# 02-MCU.net
KiCad netlist of a schematic drawn in Altium Designer
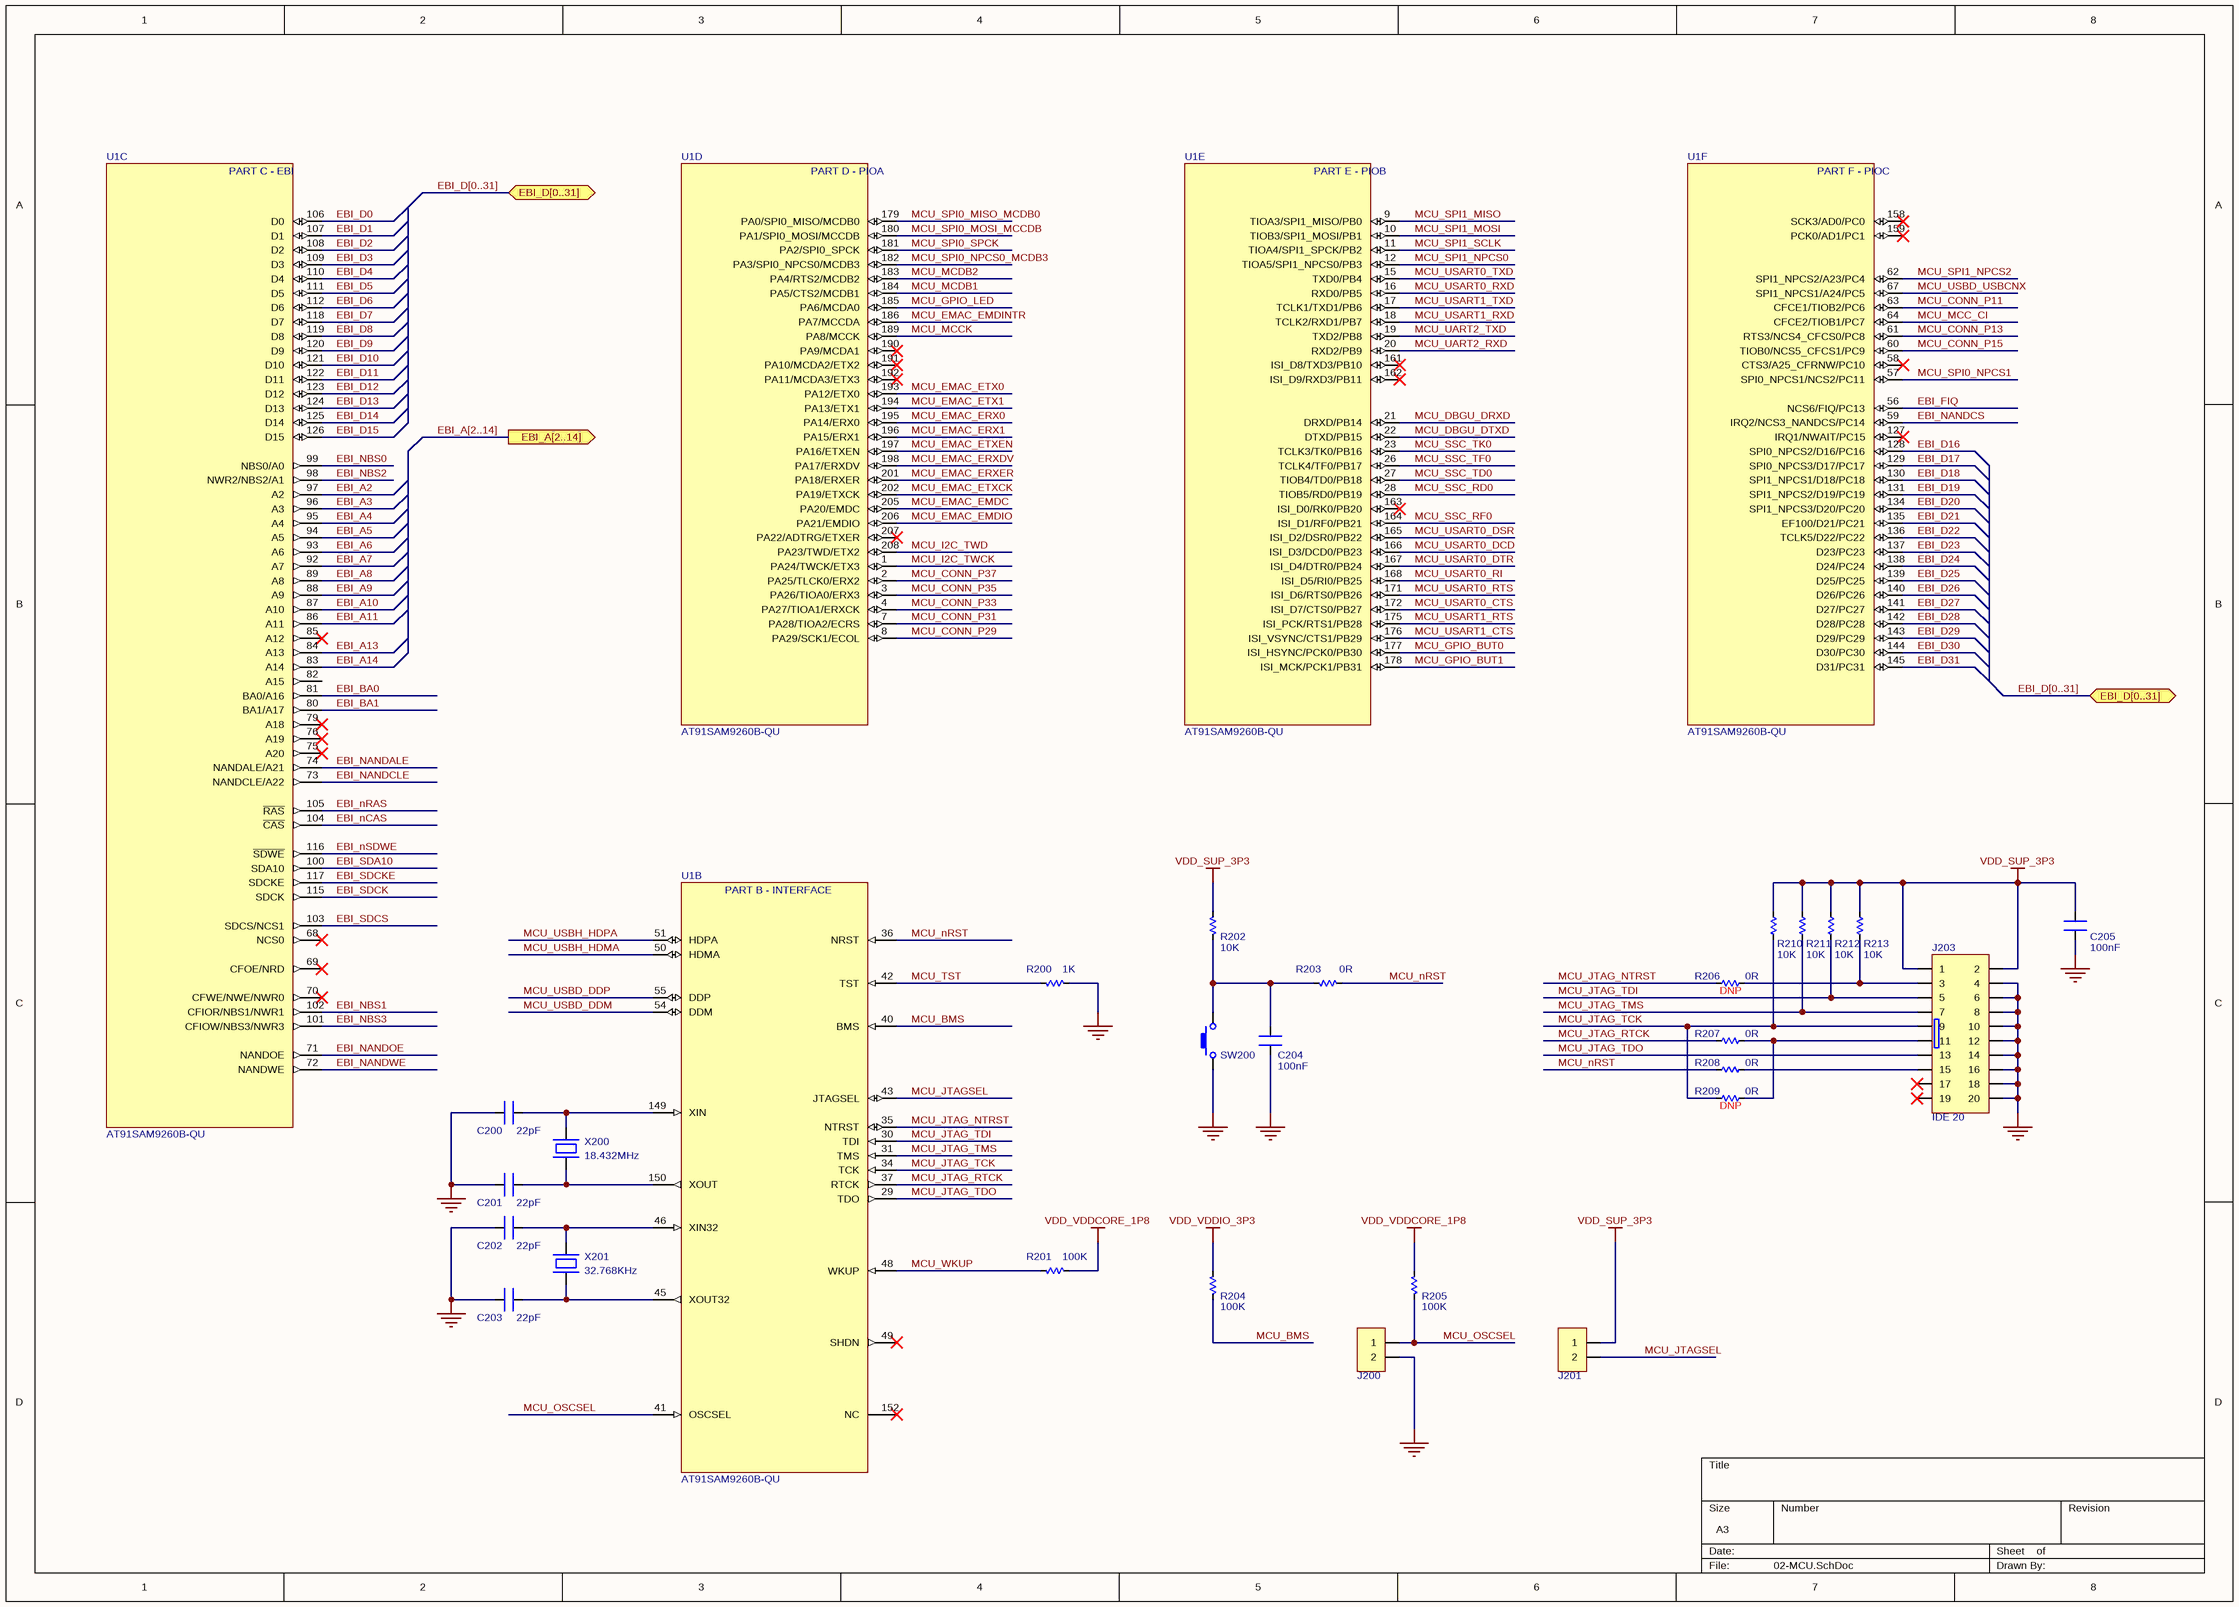
[diagram p0: 02-MCU.SchDoc]

(export (version "E")
  (design (tool "Eeschema 10.0.6"))
  (components
    (comp (ref "C200")
      (value "22pF")
      (footprint "CN-SMD-0603")
      (description "Ceramic Capacitor SMD 0603 22pF ±20% 10V")
      (fields (field (name "Comment") "Capacitor"))
      (libsource (lib "AS50") (part "Cap"))
    )
    (comp (ref "C201")
      (value "22pF")
      (footprint "CN-SMD-0603")
      (description "Ceramic Capacitor SMD 0603 22pF ±20% 10V")
      (fields (field (name "Comment") "Capacitor"))
      (libsource (lib "AS50") (part "Cap"))
    )
    (comp (ref "C202")
      (value "22pF")
      (footprint "CN-SMD-0603")
      (description "Ceramic Capacitor SMD 0603 22pF ±20% 10V")
      (fields (field (name "Comment") "Capacitor"))
      (libsource (lib "AS50") (part "Cap"))
    )
    (comp (ref "C203")
      (value "22pF")
      (footprint "CN-SMD-0603")
      (description "Ceramic Capacitor SMD 0603 22pF ±20% 10V")
      (fields (field (name "Comment") "Capacitor"))
      (libsource (lib "AS50") (part "Cap"))
    )
    (comp (ref "C204")
      (value "100nF")
      (footprint "CN-SMD-0603")
      (description "Ceramic Capacitor SMD 0603 100nF ±20% 10V")
      (fields (field (name "Comment") "Capacitor"))
      (libsource (lib "AS50") (part "Cap"))
    )
    (comp (ref "C205")
      (value "100nF")
      (footprint "CN-SMD-0603")
      (description "Ceramic Capacitor SMD 0603 100nF ±20% 10V")
      (fields (field (name "Comment") "Capacitor"))
      (libsource (lib "AS50") (part "Cap"))
    )
    (comp (ref "J200")
      (value "JP2")
      (footprint "JP2-C1T")
      (description "Single 2-pin jumper")
      (libsource (lib "AS50") (part "JP2"))
    )
    (comp (ref "J201")
      (value "JP2")
      (footprint "JP2-C1T")
      (description "Single 2-pin jumper")
      (libsource (lib "AS50") (part "JP2"))
    )
    (comp (ref "J203")
      (value "IDE 20")
      (footprint "IDE-20V")
      (description "IDE-20 male 2.54mm right-angle header")
      (libsource (lib "AS50") (part "IDE 20"))
    )
    (comp (ref "R200")
      (value "1K")
      (footprint "RES-SMD-0603")
      (description "Resistor SMD 0603 1K 1% 0.1W")
      (fields (field (name "Comment") "Resistor"))
      (libsource (lib "AS50") (part "Res"))
    )
    (comp (ref "R201")
      (value "100K")
      (footprint "RES-SMD-0603")
      (description "Resistor SMD 0603 100K 1% 0.1W")
      (fields (field (name "Comment") "Resistor"))
      (libsource (lib "AS50") (part "Res"))
    )
    (comp (ref "R202")
      (value "10K")
      (footprint "RES-SMD-0603")
      (description "Resistor SMD 0603 10K 1% 0.1W")
      (fields (field (name "Comment") "Resistor"))
      (libsource (lib "AS50") (part "Res"))
    )
    (comp (ref "R203")
      (value "0R")
      (footprint "RES-SMD-0603")
      (description "Resistor SMD 0603 0R 1% 0.1W")
      (fields (field (name "Comment") "Resistor"))
      (libsource (lib "AS50") (part "Res"))
    )
    (comp (ref "R204")
      (value "100K")
      (footprint "RES-SMD-0603")
      (description "Resistor SMD 0603 100K 1% 0.1W")
      (fields (field (name "Comment") "Resistor"))
      (libsource (lib "AS50") (part "Res"))
    )
    (comp (ref "R205")
      (value "100K")
      (footprint "RES-SMD-0603")
      (description "Resistor SMD 0603 100K 1% 0.1W")
      (fields (field (name "Comment") "Resistor"))
      (libsource (lib "AS50") (part "Res"))
    )
    (comp (ref "R206")
      (value "0R")
      (footprint "RES-SMD-0603")
      (description "Resistor SMD 0603 0R 1% 0.1W")
      (fields (field (name "Comment") "Resistor"))
      (libsource (lib "AS50") (part "Res"))
    )
    (comp (ref "R207")
      (value "0R")
      (footprint "RES-SMD-0603")
      (description "Resistor SMD 0603 0R 1% 0.1W")
      (fields (field (name "Comment") "Resistor"))
      (libsource (lib "AS50") (part "Res"))
    )
    (comp (ref "R208")
      (value "0R")
      (footprint "RES-SMD-0603")
      (description "Resistor SMD 0603 0R 1% 0.1W")
      (fields (field (name "Comment") "Resistor"))
      (libsource (lib "AS50") (part "Res"))
    )
    (comp (ref "R209")
      (value "0R")
      (footprint "RES-SMD-0603")
      (description "Resistor SMD 0603 0R 1% 0.1W")
      (fields (field (name "Comment") "Resistor"))
      (libsource (lib "AS50") (part "Res"))
    )
    (comp (ref "R210")
      (value "10K")
      (footprint "RES-SMD-0603")
      (description "Resistor SMD 0603 10K 1% 0.1W")
      (fields (field (name "Comment") "Resistor"))
      (libsource (lib "AS50") (part "Res"))
    )
    (comp (ref "R211")
      (value "10K")
      (footprint "RES-SMD-0603")
      (description "Resistor SMD 0603 10K 1% 0.1W")
      (fields (field (name "Comment") "Resistor"))
      (libsource (lib "AS50") (part "Res"))
    )
    (comp (ref "R212")
      (value "10K")
      (footprint "RES-SMD-0603")
      (description "Resistor SMD 0603 10K 1% 0.1W")
      (fields (field (name "Comment") "Resistor"))
      (libsource (lib "AS50") (part "Res"))
    )
    (comp (ref "R213")
      (value "10K")
      (footprint "RES-SMD-0603")
      (description "Resistor SMD 0603 10K 1% 0.1W")
      (fields (field (name "Comment") "Resistor"))
      (libsource (lib "AS50") (part "Res"))
    )
    (comp (ref "SW200")
      (value "SW2")
      (footprint "SW2-SMD-3x4x2M")
      (description "Switch 2-pin SMD 3x4x2mm")
      (libsource (lib "AS50") (part "SW2"))
    )
    (comp (ref "U1")
      (value "AT91SAM9260B-QU")
      (footprint "PQFP50P3060X3060X410-208N")
      (description "AT91 Series 180 MHz 32 kB Flash 8 kB SRAM 32-Bit Microcontroller - PQFP-208")
      (fields (field (name "MF") "Microchip"))
      (libsource (lib "AS50") (part "AT91SAM9260B-QU"))
    )
    (comp (ref "X200")
      (value "18.432MHz")
      (footprint "XT-SMD-5032-2P")
      (description "Crystal Oscillator 18.432MHz SMD-5032 2-pin")
      (fields (field (name "Comment") "Crystal"))
      (libsource (lib "AS50") (part "XT2"))
    )
    (comp (ref "X201")
      (value "32.768KHz")
      (footprint "XT-SMD-FC-135")
      (description "Crystal Oscillator 32.768KHz FC-135 2-pin")
      (fields (field (name "Comment") "Crystal"))
      (libsource (lib "AS50") (part "XT2"))
    )
  )
  (nets
    (net (code "2") (name "/EBI_A2") (class "Default")
      (node (ref "U1") (pin "97") (pinfunction "A2_97") (pintype "output"))
    )
    (net (code "3") (name "/EBI_A3") (class "Default")
      (node (ref "U1") (pin "96") (pinfunction "A3_96") (pintype "output"))
    )
    (net (code "4") (name "/EBI_A4") (class "Default")
      (node (ref "U1") (pin "95") (pinfunction "A4_95") (pintype "output"))
    )
    (net (code "5") (name "/EBI_A5") (class "Default")
      (node (ref "U1") (pin "94") (pinfunction "A5_94") (pintype "output"))
    )
    (net (code "6") (name "/EBI_A6") (class "Default")
      (node (ref "U1") (pin "93") (pinfunction "A6_93") (pintype "output"))
    )
    (net (code "7") (name "/EBI_A7") (class "Default")
      (node (ref "U1") (pin "92") (pinfunction "A7_92") (pintype "output"))
    )
    (net (code "8") (name "/EBI_A8") (class "Default")
      (node (ref "U1") (pin "89") (pinfunction "A8_89") (pintype "output"))
    )
    (net (code "9") (name "/EBI_A9") (class "Default")
      (node (ref "U1") (pin "88") (pinfunction "A9_88") (pintype "output"))
    )
    (net (code "10") (name "/EBI_A10") (class "Default")
      (node (ref "U1") (pin "87") (pinfunction "A10_87") (pintype "output"))
    )
    (net (code "11") (name "/EBI_A11") (class "Default")
      (node (ref "U1") (pin "86") (pinfunction "A11_86") (pintype "output"))
    )
    (net (code "12") (name "/EBI_A13") (class "Default")
      (node (ref "U1") (pin "84") (pinfunction "A13_84") (pintype "output"))
    )
    (net (code "13") (name "/EBI_A14") (class "Default")
      (node (ref "U1") (pin "83") (pinfunction "A14_83") (pintype "output"))
    )
    (net (code "15") (name "/EBI_BA0") (class "Default")
      (node (ref "U1") (pin "81") (pinfunction "BA0/A16_81") (pintype "output"))
    )
    (net (code "16") (name "/EBI_BA1") (class "Default")
      (node (ref "U1") (pin "80") (pinfunction "BA1/A17_80") (pintype "output"))
    )
    (net (code "17") (name "/EBI_D0") (class "Default")
      (node (ref "U1") (pin "106") (pinfunction "D0_106") (pintype "bidirectional"))
    )
    (net (code "18") (name "/EBI_D1") (class "Default")
      (node (ref "U1") (pin "107") (pinfunction "D1_107") (pintype "bidirectional"))
    )
    (net (code "19") (name "/EBI_D2") (class "Default")
      (node (ref "U1") (pin "108") (pinfunction "D2_108") (pintype "bidirectional"))
    )
    (net (code "20") (name "/EBI_D3") (class "Default")
      (node (ref "U1") (pin "109") (pinfunction "D3_109") (pintype "bidirectional"))
    )
    (net (code "21") (name "/EBI_D4") (class "Default")
      (node (ref "U1") (pin "110") (pinfunction "D4_110") (pintype "bidirectional"))
    )
    (net (code "22") (name "/EBI_D5") (class "Default")
      (node (ref "U1") (pin "111") (pinfunction "D5_111") (pintype "bidirectional"))
    )
    (net (code "23") (name "/EBI_D6") (class "Default")
      (node (ref "U1") (pin "112") (pinfunction "D6_112") (pintype "bidirectional"))
    )
    (net (code "24") (name "/EBI_D7") (class "Default")
      (node (ref "U1") (pin "118") (pinfunction "D7_118") (pintype "bidirectional"))
    )
    (net (code "25") (name "/EBI_D8") (class "Default")
      (node (ref "U1") (pin "119") (pinfunction "D8_119") (pintype "bidirectional"))
    )
    (net (code "26") (name "/EBI_D9") (class "Default")
      (node (ref "U1") (pin "120") (pinfunction "D9_120") (pintype "bidirectional"))
    )
    (net (code "27") (name "/EBI_D10") (class "Default")
      (node (ref "U1") (pin "121") (pinfunction "D10_121") (pintype "bidirectional"))
    )
    (net (code "28") (name "/EBI_D11") (class "Default")
      (node (ref "U1") (pin "122") (pinfunction "D11_122") (pintype "bidirectional"))
    )
    (net (code "29") (name "/EBI_D12") (class "Default")
      (node (ref "U1") (pin "123") (pinfunction "D12_123") (pintype "bidirectional"))
    )
    (net (code "30") (name "/EBI_D13") (class "Default")
      (node (ref "U1") (pin "124") (pinfunction "D13_124") (pintype "bidirectional"))
    )
    (net (code "31") (name "/EBI_D14") (class "Default")
      (node (ref "U1") (pin "125") (pinfunction "D14_125") (pintype "bidirectional"))
    )
    (net (code "32") (name "/EBI_D15") (class "Default")
      (node (ref "U1") (pin "126") (pinfunction "D15_126") (pintype "bidirectional"))
    )
    (net (code "33") (name "/EBI_D16") (class "Default")
      (node (ref "U1") (pin "128") (pinfunction "SPI0_NPCS2/D16/PC16_128") (pintype "bidirectional"))
    )
    (net (code "34") (name "/EBI_D17") (class "Default")
      (node (ref "U1") (pin "129") (pinfunction "SPI0_NPCS3/D17/PC17_129") (pintype "bidirectional"))
    )
    (net (code "35") (name "/EBI_D18") (class "Default")
      (node (ref "U1") (pin "130") (pinfunction "SPI1_NPCS1/D18/PC18_130") (pintype "bidirectional"))
    )
    (net (code "36") (name "/EBI_D19") (class "Default")
      (node (ref "U1") (pin "131") (pinfunction "SPI1_NPCS2/D19/PC19_131") (pintype "bidirectional"))
    )
    (net (code "37") (name "/EBI_D20") (class "Default")
      (node (ref "U1") (pin "134") (pinfunction "SPI1_NPCS3/D20/PC20_134") (pintype "bidirectional"))
    )
    (net (code "38") (name "/EBI_D21") (class "Default")
      (node (ref "U1") (pin "135") (pinfunction "EF100/D21/PC21_135") (pintype "bidirectional"))
    )
    (net (code "39") (name "/EBI_D22") (class "Default")
      (node (ref "U1") (pin "136") (pinfunction "TCLK5/D22/PC22_136") (pintype "bidirectional"))
    )
    (net (code "40") (name "/EBI_D23") (class "Default")
      (node (ref "U1") (pin "137") (pinfunction "D23/PC23_137") (pintype "bidirectional"))
    )
    (net (code "41") (name "/EBI_D24") (class "Default")
      (node (ref "U1") (pin "138") (pinfunction "D24/PC24_138") (pintype "bidirectional"))
    )
    (net (code "42") (name "/EBI_D25") (class "Default")
      (node (ref "U1") (pin "139") (pinfunction "D25/PC25_139") (pintype "bidirectional"))
    )
    (net (code "43") (name "/EBI_D26") (class "Default")
      (node (ref "U1") (pin "140") (pinfunction "D26/PC26_140") (pintype "bidirectional"))
    )
    (net (code "44") (name "/EBI_D27") (class "Default")
      (node (ref "U1") (pin "141") (pinfunction "D27/PC27_141") (pintype "bidirectional"))
    )
    (net (code "45") (name "/EBI_D28") (class "Default")
      (node (ref "U1") (pin "142") (pinfunction "D28/PC28_142") (pintype "bidirectional"))
    )
    (net (code "46") (name "/EBI_D29") (class "Default")
      (node (ref "U1") (pin "143") (pinfunction "D29/PC29_143") (pintype "bidirectional"))
    )
    (net (code "47") (name "/EBI_D30") (class "Default")
      (node (ref "U1") (pin "144") (pinfunction "D30/PC30_144") (pintype "bidirectional"))
    )
    (net (code "48") (name "/EBI_D31") (class "Default")
      (node (ref "U1") (pin "145") (pinfunction "D31/PC31_145") (pintype "bidirectional"))
    )
    (net (code "50") (name "/EBI_FIQ") (class "Default")
      (node (ref "U1") (pin "56") (pinfunction "NCS6/FIQ/PC13_56") (pintype "bidirectional"))
    )
    (net (code "51") (name "/EBI_NANDALE") (class "Default")
      (node (ref "U1") (pin "74") (pinfunction "A21_74") (pintype "output"))
    )
    (net (code "52") (name "/EBI_NANDCLE") (class "Default")
      (node (ref "U1") (pin "73") (pinfunction "A22_73") (pintype "output"))
    )
    (net (code "53") (name "/EBI_NANDCS") (class "Default")
      (node (ref "U1") (pin "59") (pinfunction "IRQ2/NCS3_NANDCS/PC14_59") (pintype "bidirectional"))
    )
    (net (code "54") (name "/EBI_NANDOE") (class "Default")
      (node (ref "U1") (pin "71") (pinfunction "NANDOE_71") (pintype "output"))
    )
    (net (code "55") (name "/EBI_NANDWE") (class "Default")
      (node (ref "U1") (pin "72") (pinfunction "NANDWE_72") (pintype "output"))
    )
    (net (code "56") (name "/EBI_NBS0") (class "Default")
      (node (ref "U1") (pin "99") (pinfunction "NBS0/A0_99") (pintype "output"))
    )
    (net (code "57") (name "/EBI_NBS1") (class "Default")
      (node (ref "U1") (pin "102") (pinfunction "CFIOR/NBS1/NWR1_102") (pintype "output"))
    )
    (net (code "58") (name "/EBI_NBS2") (class "Default")
      (node (ref "U1") (pin "98") (pinfunction "NWR2/NBS2/A1_98") (pintype "output"))
    )
    (net (code "59") (name "/EBI_NBS3") (class "Default")
      (node (ref "U1") (pin "101") (pinfunction "CFIOW/NBS3/NWR3_101") (pintype "output"))
    )
    (net (code "60") (name "/EBI_SDA10") (class "Default")
      (node (ref "U1") (pin "100") (pinfunction "SDA10_100") (pintype "output"))
    )
    (net (code "61") (name "/EBI_SDCK") (class "Default")
      (node (ref "U1") (pin "115") (pinfunction "SDCK_115") (pintype "output"))
    )
    (net (code "62") (name "/EBI_SDCKE") (class "Default")
      (node (ref "U1") (pin "117") (pinfunction "SDCKE_117") (pintype "output"))
    )
    (net (code "63") (name "/EBI_SDCS") (class "Default")
      (node (ref "U1") (pin "103") (pinfunction "SDCS/NCS1_103") (pintype "output"))
    )
    (net (code "64") (name "/EBI_nCAS") (class "Default")
      (node (ref "U1") (pin "104") (pinfunction "~{CAS}_104") (pintype "output"))
    )
    (net (code "65") (name "/EBI_nRAS") (class "Default")
      (node (ref "U1") (pin "105") (pinfunction "~{RAS}_105") (pintype "output"))
    )
    (net (code "66") (name "/EBI_nSDWE") (class "Default")
      (node (ref "U1") (pin "116") (pinfunction "~{SDWE}_116") (pintype "output"))
    )
    (net (code "67") (name "/MCU_BMS") (class "Default")
      (node (ref "R204") (pin "2") (pinfunction "2_2") (pintype "passive"))
      (node (ref "U1") (pin "40") (pinfunction "BMS_40") (pintype "input"))
    )
    (net (code "68") (name "/MCU_CONN_P11") (class "Default")
      (node (ref "U1") (pin "63") (pinfunction "CFCE1/TIOB2/PC6_63") (pintype "bidirectional"))
    )
    (net (code "69") (name "/MCU_CONN_P13") (class "Default")
      (node (ref "U1") (pin "61") (pinfunction "RTS3/NCS4_CFCS0/PC8_61") (pintype "bidirectional"))
    )
    (net (code "70") (name "/MCU_CONN_P15") (class "Default")
      (node (ref "U1") (pin "60") (pinfunction "TIOB0/NCS5_CFCS1/PC9_60") (pintype "bidirectional"))
    )
    (net (code "71") (name "/MCU_CONN_P29") (class "Default")
      (node (ref "U1") (pin "8") (pinfunction "PA29/SCK1/ECOL_8") (pintype "bidirectional"))
    )
    (net (code "72") (name "/MCU_CONN_P31") (class "Default")
      (node (ref "U1") (pin "7") (pinfunction "PA28/TIOA2/ECRS_7") (pintype "bidirectional"))
    )
    (net (code "73") (name "/MCU_CONN_P33") (class "Default")
      (node (ref "U1") (pin "4") (pinfunction "PA27/TIOA1/ERXCK_4") (pintype "bidirectional"))
    )
    (net (code "74") (name "/MCU_CONN_P35") (class "Default")
      (node (ref "U1") (pin "3") (pinfunction "PA26/TIOA0/ERX3_3") (pintype "bidirectional"))
    )
    (net (code "75") (name "/MCU_CONN_P37") (class "Default")
      (node (ref "U1") (pin "2") (pinfunction "PA25/TLCK0/ERX2_2") (pintype "bidirectional"))
    )
    (net (code "76") (name "/MCU_DBGU_DRXD") (class "Default")
      (node (ref "U1") (pin "21") (pinfunction "DRXD/PB14_21") (pintype "bidirectional"))
    )
    (net (code "77") (name "/MCU_DBGU_DTXD") (class "Default")
      (node (ref "U1") (pin "22") (pinfunction "DTXD/PB15_22") (pintype "bidirectional"))
    )
    (net (code "78") (name "/MCU_EMAC_EMDC") (class "Default")
      (node (ref "U1") (pin "205") (pinfunction "PA20/EMDC_205") (pintype "bidirectional"))
    )
    (net (code "79") (name "/MCU_EMAC_EMDINTR") (class "Default")
      (node (ref "U1") (pin "186") (pinfunction "PA7/MCCDA_186") (pintype "bidirectional"))
    )
    (net (code "80") (name "/MCU_EMAC_EMDIO") (class "Default")
      (node (ref "U1") (pin "206") (pinfunction "PA21/EMDIO_206") (pintype "bidirectional"))
    )
    (net (code "81") (name "/MCU_EMAC_ERX0") (class "Default")
      (node (ref "U1") (pin "195") (pinfunction "PA14/ERX0_195") (pintype "bidirectional"))
    )
    (net (code "82") (name "/MCU_EMAC_ERX1") (class "Default")
      (node (ref "U1") (pin "196") (pinfunction "PA15/ERX1_196") (pintype "bidirectional"))
    )
    (net (code "83") (name "/MCU_EMAC_ERXDV") (class "Default")
      (node (ref "U1") (pin "198") (pinfunction "PA17/ERXDV_198") (pintype "bidirectional"))
    )
    (net (code "84") (name "/MCU_EMAC_ERXER") (class "Default")
      (node (ref "U1") (pin "201") (pinfunction "PA18/ERXER_201") (pintype "bidirectional"))
    )
    (net (code "85") (name "/MCU_EMAC_ETX0") (class "Default")
      (node (ref "U1") (pin "193") (pinfunction "PA12/ETX0_193") (pintype "bidirectional"))
    )
    (net (code "86") (name "/MCU_EMAC_ETX1") (class "Default")
      (node (ref "U1") (pin "194") (pinfunction "PA13/ETX1_194") (pintype "bidirectional"))
    )
    (net (code "87") (name "/MCU_EMAC_ETXCK") (class "Default")
      (node (ref "U1") (pin "202") (pinfunction "PA19/ETXCK_202") (pintype "bidirectional"))
    )
    (net (code "88") (name "/MCU_EMAC_ETXEN") (class "Default")
      (node (ref "U1") (pin "197") (pinfunction "PA16/ETXEN_197") (pintype "bidirectional"))
    )
    (net (code "89") (name "/MCU_GPIO_BUT0") (class "Default")
      (node (ref "U1") (pin "177") (pinfunction "ISI_HSYNC/PCK0/PB30_177") (pintype "bidirectional"))
    )
    (net (code "90") (name "/MCU_GPIO_BUT1") (class "Default")
      (node (ref "U1") (pin "178") (pinfunction "ISI_MCK/PCK1/PB31_178") (pintype "bidirectional"))
    )
    (net (code "91") (name "/MCU_GPIO_LED") (class "Default")
      (node (ref "U1") (pin "185") (pinfunction "PA6/MCDA0_185") (pintype "bidirectional"))
    )
    (net (code "92") (name "/MCU_I2C_TWCK") (class "Default")
      (node (ref "U1") (pin "1") (pinfunction "PA24/TWCK/ETX3_1") (pintype "bidirectional"))
    )
    (net (code "93") (name "/MCU_I2C_TWD") (class "Default")
      (node (ref "U1") (pin "208") (pinfunction "PA23/TWD/ETX2_208") (pintype "bidirectional"))
    )
    (net (code "94") (name "/MCU_JTAGSEL") (class "Default")
      (node (ref "J201") (pin "2") (pinfunction "2_2") (pintype "passive"))
      (node (ref "U1") (pin "43") (pinfunction "JTAGSEL_43") (pintype "bidirectional"))
    )
    (net (code "95") (name "/MCU_JTAG_NTRST") (class "Default")
      (node (ref "R206") (pin "2") (pinfunction "2_2") (pintype "passive"))
      (node (ref "U1") (pin "35") (pinfunction "NTRST_35") (pintype "bidirectional"))
    )
    (net (code "96") (name "/MCU_JTAG_RTCK") (class "Default")
      (node (ref "R207") (pin "2") (pinfunction "2_2") (pintype "passive"))
      (node (ref "U1") (pin "37") (pinfunction "RTCK_37") (pintype "output"))
    )
    (net (code "97") (name "/MCU_JTAG_TCK") (class "Default")
      (node (ref "J203") (pin "9") (pinfunction "9_9") (pintype "passive"))
      (node (ref "R209") (pin "2") (pinfunction "2_2") (pintype "passive"))
      (node (ref "R210") (pin "2") (pinfunction "2_2") (pintype "passive"))
      (node (ref "U1") (pin "34") (pinfunction "TCK_34") (pintype "input"))
    )
    (net (code "98") (name "/MCU_JTAG_TDI") (class "Default")
      (node (ref "J203") (pin "5") (pinfunction "5_5") (pintype "passive"))
      (node (ref "R212") (pin "2") (pinfunction "2_2") (pintype "passive"))
      (node (ref "U1") (pin "30") (pinfunction "TDI_30") (pintype "input"))
    )
    (net (code "99") (name "/MCU_JTAG_TDO") (class "Default")
      (node (ref "J203") (pin "13") (pinfunction "13_13") (pintype "passive"))
      (node (ref "U1") (pin "29") (pinfunction "TDO_29") (pintype "output"))
    )
    (net (code "100") (name "/MCU_JTAG_TMS") (class "Default")
      (node (ref "J203") (pin "7") (pinfunction "7_7") (pintype "passive"))
      (node (ref "R211") (pin "2") (pinfunction "2_2") (pintype "passive"))
      (node (ref "U1") (pin "31") (pinfunction "TMS_31") (pintype "input"))
    )
    (net (code "101") (name "/MCU_MCCK") (class "Default")
      (node (ref "U1") (pin "189") (pinfunction "PA8/MCCK_189") (pintype "bidirectional"))
    )
    (net (code "102") (name "/MCU_MCC_CI") (class "Default")
      (node (ref "U1") (pin "64") (pinfunction "CFCE2/TIOB1/PC7_64") (pintype "bidirectional"))
    )
    (net (code "103") (name "/MCU_MCDB1") (class "Default")
      (node (ref "U1") (pin "184") (pinfunction "PA5/CTS2/MCDB1_184") (pintype "bidirectional"))
    )
    (net (code "104") (name "/MCU_MCDB2") (class "Default")
      (node (ref "U1") (pin "183") (pinfunction "PA4/RTS2/MCDB2_183") (pintype "bidirectional"))
    )
    (net (code "105") (name "/MCU_OSCSEL") (class "Default")
      (node (ref "J200") (pin "1") (pinfunction "1_1") (pintype "passive"))
      (node (ref "R205") (pin "2") (pinfunction "2_2") (pintype "passive"))
      (node (ref "U1") (pin "41") (pinfunction "OSCSEL_41") (pintype "input"))
    )
    (net (code "106") (name "/MCU_SPI0_MISO_MCDB0") (class "Default")
      (node (ref "U1") (pin "179") (pinfunction "PA0/SPI0_MISO/MCDB0_179") (pintype "bidirectional"))
    )
    (net (code "107") (name "/MCU_SPI0_MOSI_MCCDB") (class "Default")
      (node (ref "U1") (pin "180") (pinfunction "PA1/SPI0_MOSI/MCCDB_180") (pintype "bidirectional"))
    )
    (net (code "108") (name "/MCU_SPI0_NPCS0_MCDB3") (class "Default")
      (node (ref "U1") (pin "182") (pinfunction "PA3/SPI0_NPCS0/MCDB3_182") (pintype "bidirectional"))
    )
    (net (code "109") (name "/MCU_SPI0_NPCS1") (class "Default")
      (node (ref "U1") (pin "57") (pinfunction "SPI0_NPCS1/NCS2/PC11_57") (pintype "bidirectional"))
    )
    (net (code "110") (name "/MCU_SPI0_SPCK") (class "Default")
      (node (ref "U1") (pin "181") (pinfunction "PA2/SPI0_SPCK_181") (pintype "bidirectional"))
    )
    (net (code "111") (name "/MCU_SPI1_MISO") (class "Default")
      (node (ref "U1") (pin "9") (pinfunction "TIOA3/SPI1_MISO/PB0_9") (pintype "bidirectional"))
    )
    (net (code "112") (name "/MCU_SPI1_MOSI") (class "Default")
      (node (ref "U1") (pin "10") (pinfunction "TIOB3/SPI1_MOSI/PB1_10") (pintype "bidirectional"))
    )
    (net (code "113") (name "/MCU_SPI1_NPCS0") (class "Default")
      (node (ref "U1") (pin "12") (pinfunction "TIOA5/SPI1_NPCS0/PB3_12") (pintype "bidirectional"))
    )
    (net (code "114") (name "/MCU_SPI1_NPCS2") (class "Default")
      (node (ref "U1") (pin "62") (pinfunction "SPI1_NPCS2/A23/PC4_62") (pintype "bidirectional"))
    )
    (net (code "115") (name "/MCU_SPI1_SCLK") (class "Default")
      (node (ref "U1") (pin "11") (pinfunction "TIOA4/SPI1_SPCK/PB2_11") (pintype "bidirectional"))
    )
    (net (code "116") (name "/MCU_SSC_RD0") (class "Default")
      (node (ref "U1") (pin "28") (pinfunction "TIOB5/RD0/PB19_28") (pintype "bidirectional"))
    )
    (net (code "117") (name "/MCU_SSC_RF0") (class "Default")
      (node (ref "U1") (pin "164") (pinfunction "ISI_D1/RF0/PB21_164") (pintype "bidirectional"))
    )
    (net (code "118") (name "/MCU_SSC_TD0") (class "Default")
      (node (ref "U1") (pin "27") (pinfunction "TIOB4/TD0/PB18_27") (pintype "bidirectional"))
    )
    (net (code "119") (name "/MCU_SSC_TF0") (class "Default")
      (node (ref "U1") (pin "26") (pinfunction "TCLK4/TF0/PB17_26") (pintype "bidirectional"))
    )
    (net (code "120") (name "/MCU_SSC_TK0") (class "Default")
      (node (ref "U1") (pin "23") (pinfunction "TCLK3/TK0/PB16_23") (pintype "bidirectional"))
    )
    (net (code "121") (name "/MCU_TST") (class "Default")
      (node (ref "R200") (pin "2") (pinfunction "2_2") (pintype "passive"))
      (node (ref "U1") (pin "42") (pinfunction "TST_42") (pintype "input"))
    )
    (net (code "122") (name "/MCU_UART2_RXD") (class "Default")
      (node (ref "U1") (pin "20") (pinfunction "RXD2/PB9_20") (pintype "bidirectional"))
    )
    (net (code "123") (name "/MCU_UART2_TXD") (class "Default")
      (node (ref "U1") (pin "19") (pinfunction "TXD2/PB8_19") (pintype "bidirectional"))
    )
    (net (code "124") (name "/MCU_USART0_CTS") (class "Default")
      (node (ref "U1") (pin "172") (pinfunction "ISI_D7/CTS0/PB27_172") (pintype "bidirectional"))
    )
    (net (code "125") (name "/MCU_USART0_DCD") (class "Default")
      (node (ref "U1") (pin "166") (pinfunction "ISI_D3/DCD0/PB23_166") (pintype "bidirectional"))
    )
    (net (code "126") (name "/MCU_USART0_DSR") (class "Default")
      (node (ref "U1") (pin "165") (pinfunction "ISI_D2/DSR0/PB22_165") (pintype "bidirectional"))
    )
    (net (code "127") (name "/MCU_USART0_DTR") (class "Default")
      (node (ref "U1") (pin "167") (pinfunction "ISI_D4/DTR0/PB24_167") (pintype "bidirectional"))
    )
    (net (code "128") (name "/MCU_USART0_RI") (class "Default")
      (node (ref "U1") (pin "168") (pinfunction "ISI_D5/RI0/PB25_168") (pintype "bidirectional"))
    )
    (net (code "129") (name "/MCU_USART0_RTS") (class "Default")
      (node (ref "U1") (pin "171") (pinfunction "ISI_D6/RTS0/PB26_171") (pintype "bidirectional"))
    )
    (net (code "130") (name "/MCU_USART0_RXD") (class "Default")
      (node (ref "U1") (pin "16") (pinfunction "RXD0/PB5_16") (pintype "bidirectional"))
    )
    (net (code "131") (name "/MCU_USART0_TXD") (class "Default")
      (node (ref "U1") (pin "15") (pinfunction "TXD0/PB4_15") (pintype "bidirectional"))
    )
    (net (code "132") (name "/MCU_USART1_CTS") (class "Default")
      (node (ref "U1") (pin "176") (pinfunction "ISI_VSYNC/CTS1/PB29_176") (pintype "bidirectional"))
    )
    (net (code "133") (name "/MCU_USART1_RTS") (class "Default")
      (node (ref "U1") (pin "175") (pinfunction "ISI_PCK/RTS1/PB28_175") (pintype "bidirectional"))
    )
    (net (code "134") (name "/MCU_USART1_RXD") (class "Default")
      (node (ref "U1") (pin "18") (pinfunction "TCLK2/RXD1/PB7_18") (pintype "bidirectional"))
    )
    (net (code "135") (name "/MCU_USART1_TXD") (class "Default")
      (node (ref "U1") (pin "17") (pinfunction "TCLK1/TXD1/PB6_17") (pintype "bidirectional"))
    )
    (net (code "136") (name "/MCU_USBD_DDM") (class "Default")
      (node (ref "U1") (pin "54") (pinfunction "DDM_54") (pintype "bidirectional"))
    )
    (net (code "137") (name "/MCU_USBD_DDP") (class "Default")
      (node (ref "U1") (pin "55") (pinfunction "DDP_55") (pintype "bidirectional"))
    )
    (net (code "138") (name "/MCU_USBD_USBCNX") (class "Default")
      (node (ref "U1") (pin "67") (pinfunction "SPI1_NPCS1/A24/PC5_67") (pintype "bidirectional"))
    )
    (net (code "139") (name "/MCU_USBH_HDMA") (class "Default")
      (node (ref "U1") (pin "50") (pinfunction "HDMA_50") (pintype "bidirectional"))
    )
    (net (code "140") (name "/MCU_USBH_HDPA") (class "Default")
      (node (ref "U1") (pin "51") (pinfunction "HDPA_51") (pintype "bidirectional"))
    )
    (net (code "141") (name "/MCU_WKUP") (class "Default")
      (node (ref "R201") (pin "2") (pinfunction "2_2") (pintype "passive"))
      (node (ref "U1") (pin "48") (pinfunction "WKUP_48") (pintype "input"))
    )
    (net (code "142") (name "/MCU_nRST") (class "Default")
      (node (ref "R203") (pin "2") (pinfunction "2_2") (pintype "passive"))
      (node (ref "R208") (pin "2") (pinfunction "2_2") (pintype "passive"))
      (node (ref "U1") (pin "36") (pinfunction "NRST_36") (pintype "input"))
    )
    (net (code "143") (name "GND") (class "Default")
      (node (ref "C200") (pin "2") (pinfunction "2_2") (pintype "passive"))
      (node (ref "C201") (pin "2") (pinfunction "2_2") (pintype "passive"))
      (node (ref "C202") (pin "2") (pinfunction "2_2") (pintype "passive"))
      (node (ref "C203") (pin "2") (pinfunction "2_2") (pintype "passive"))
      (node (ref "C204") (pin "1") (pinfunction "1_1") (pintype "passive"))
      (node (ref "C205") (pin "1") (pinfunction "1_1") (pintype "passive"))
      (node (ref "J200") (pin "2") (pinfunction "2_2") (pintype "passive"))
      (node (ref "J203") (pin "10") (pinfunction "10_10") (pintype "passive"))
      (node (ref "J203") (pin "12") (pinfunction "12_12") (pintype "passive"))
      (node (ref "J203") (pin "14") (pinfunction "14_14") (pintype "passive"))
      (node (ref "J203") (pin "16") (pinfunction "16_16") (pintype "passive"))
      (node (ref "J203") (pin "18") (pinfunction "18_18") (pintype "passive"))
      (node (ref "J203") (pin "20") (pinfunction "20_20") (pintype "passive"))
      (node (ref "J203") (pin "4") (pinfunction "4_4") (pintype "passive"))
      (node (ref "J203") (pin "6") (pinfunction "6_6") (pintype "passive"))
      (node (ref "J203") (pin "8") (pinfunction "8_8") (pintype "passive"))
      (node (ref "R200") (pin "1") (pinfunction "1_1") (pintype "passive"))
      (node (ref "SW200") (pin "1") (pinfunction "1_1") (pintype "passive"))
    )
    (net (code "144") (name "Net-(C204-Pad2)") (class "Default")
      (node (ref "C204") (pin "2") (pinfunction "2_2") (pintype "passive"))
      (node (ref "R202") (pin "2") (pinfunction "2_2") (pintype "passive"))
      (node (ref "R203") (pin "1") (pinfunction "1_1") (pintype "passive"))
      (node (ref "SW200") (pin "2") (pinfunction "2_2") (pintype "passive"))
    )
    (net (code "145") (name "Net-(J203-Pad3)") (class "Default")
      (node (ref "J203") (pin "3") (pinfunction "3_3") (pintype "passive"))
      (node (ref "R206") (pin "1") (pinfunction "1_1") (pintype "passive"))
      (node (ref "R213") (pin "2") (pinfunction "2_2") (pintype "passive"))
    )
    (net (code "146") (name "Net-(J203-Pad11)") (class "Default")
      (node (ref "J203") (pin "11") (pinfunction "11_11") (pintype "passive"))
      (node (ref "R207") (pin "1") (pinfunction "1_1") (pintype "passive"))
      (node (ref "R209") (pin "1") (pinfunction "1_1") (pintype "passive"))
    )
    (net (code "147") (name "Net-(J203-Pad15)") (class "Default")
      (node (ref "J203") (pin "15") (pinfunction "15_15") (pintype "passive"))
      (node (ref "R208") (pin "1") (pinfunction "1_1") (pintype "passive"))
    )
    (net (code "148") (name "Net-(U1B-XIN)") (class "Default")
      (node (ref "C200") (pin "1") (pinfunction "1_1") (pintype "passive"))
      (node (ref "U1") (pin "149") (pinfunction "XIN_149") (pintype "input"))
      (node (ref "X200") (pin "1") (pinfunction "1_1") (pintype "passive"))
    )
    (net (code "149") (name "Net-(U1B-XIN32)") (class "Default")
      (node (ref "C202") (pin "1") (pinfunction "1_1") (pintype "passive"))
      (node (ref "U1") (pin "46") (pinfunction "XIN32_46") (pintype "input"))
      (node (ref "X201") (pin "1") (pinfunction "1_1") (pintype "passive"))
    )
    (net (code "150") (name "Net-(U1B-XOUT)") (class "Default")
      (node (ref "C201") (pin "1") (pinfunction "1_1") (pintype "passive"))
      (node (ref "U1") (pin "150") (pinfunction "XOUT_150") (pintype "output"))
      (node (ref "X200") (pin "2") (pinfunction "2_2") (pintype "passive"))
    )
    (net (code "151") (name "Net-(U1B-XOUT32)") (class "Default")
      (node (ref "C203") (pin "1") (pinfunction "1_1") (pintype "passive"))
      (node (ref "U1") (pin "45") (pinfunction "XOUT32_45") (pintype "output"))
      (node (ref "X201") (pin "2") (pinfunction "2_2") (pintype "passive"))
    )
    (net (code "152") (name "VDD_SUP_3P3") (class "Default")
      (node (ref "C205") (pin "2") (pinfunction "2_2") (pintype "passive"))
      (node (ref "J201") (pin "1") (pinfunction "1_1") (pintype "passive"))
      (node (ref "J203") (pin "1") (pinfunction "1_1") (pintype "passive"))
      (node (ref "J203") (pin "2") (pinfunction "2_2") (pintype "passive"))
      (node (ref "R202") (pin "1") (pinfunction "1_1") (pintype "passive"))
      (node (ref "R210") (pin "1") (pinfunction "1_1") (pintype "passive"))
      (node (ref "R211") (pin "1") (pinfunction "1_1") (pintype "passive"))
      (node (ref "R212") (pin "1") (pinfunction "1_1") (pintype "passive"))
      (node (ref "R213") (pin "1") (pinfunction "1_1") (pintype "passive"))
    )
    (net (code "153") (name "VDD_VDDCORE_1P8") (class "Default")
      (node (ref "R201") (pin "1") (pinfunction "1_1") (pintype "passive"))
      (node (ref "R205") (pin "1") (pinfunction "1_1") (pintype "passive"))
    )
    (net (code "154") (name "VDD_VDDIO_3P3") (class "Default")
      (node (ref "R204") (pin "1") (pinfunction "1_1") (pintype "passive"))
    )
    (net (code "155") (name "unconnected-(J203-Pad17)") (class "Default")
      (node (ref "J203") (pin "17") (pinfunction "17_17") (pintype "passive+no_connect"))
    )
    (net (code "156") (name "unconnected-(J203-Pad19)") (class "Default")
      (node (ref "J203") (pin "19") (pinfunction "19_19") (pintype "passive+no_connect"))
    )
    (net (code "157") (name "unconnected-(U1B-NC-Pad152)") (class "Default")
      (node (ref "U1") (pin "152") (pinfunction "NC_152") (pintype "passive+no_connect"))
    )
    (net (code "158") (name "unconnected-(U1B-SHDN-Pad49)") (class "Default")
      (node (ref "U1") (pin "49") (pinfunction "SHDN_49") (pintype "output+no_connect"))
    )
    (net (code "159") (name "unconnected-(U1C-A12-Pad85)") (class "Default")
      (node (ref "U1") (pin "85") (pinfunction "A12_85") (pintype "output+no_connect"))
    )
    (net (code "160") (name "unconnected-(U1C-A15-Pad82)") (class "Default")
      (node (ref "U1") (pin "82") (pinfunction "A15_82") (pintype "output"))
    )
    (net (code "161") (name "unconnected-(U1C-A18-Pad79)") (class "Default")
      (node (ref "U1") (pin "79") (pinfunction "A18_79") (pintype "output+no_connect"))
    )
    (net (code "162") (name "unconnected-(U1C-A19-Pad76)") (class "Default")
      (node (ref "U1") (pin "76") (pinfunction "A19_76") (pintype "output+no_connect"))
    )
    (net (code "163") (name "unconnected-(U1C-A20-Pad75)") (class "Default")
      (node (ref "U1") (pin "75") (pinfunction "A20_75") (pintype "output+no_connect"))
    )
    (net (code "164") (name "unconnected-(U1C-CFOE{slash}NRD-Pad69)") (class "Default")
      (node (ref "U1") (pin "69") (pinfunction "CFOE/NRD_69") (pintype "output+no_connect"))
    )
    (net (code "165") (name "unconnected-(U1C-CFWE{slash}NWE{slash}NWR0-Pad70)") (class "Default")
      (node (ref "U1") (pin "70") (pinfunction "CFWE/NWE/NWR0_70") (pintype "output+no_connect"))
    )
    (net (code "166") (name "unconnected-(U1C-NCSO-Pad68)") (class "Default")
      (node (ref "U1") (pin "68") (pinfunction "NCSO_68") (pintype "output+no_connect"))
    )
    (net (code "167") (name "unconnected-(U1D-PA9{slash}MCDA1-Pad190)") (class "Default")
      (node (ref "U1") (pin "190") (pinfunction "PA9/MCDA1_190") (pintype "bidirectional+no_connect"))
    )
    (net (code "168") (name "unconnected-(U1D-PA10{slash}MCDA2{slash}ETX2-Pad191)") (class "Default")
      (node (ref "U1") (pin "191") (pinfunction "PA10/MCDA2/ETX2_191") (pintype "bidirectional+no_connect"))
    )
    (net (code "169") (name "unconnected-(U1D-PA11{slash}MCDA3{slash}ETX3-Pad192)") (class "Default")
      (node (ref "U1") (pin "192") (pinfunction "PA11/MCDA3/ETX3_192") (pintype "bidirectional+no_connect"))
    )
    (net (code "170") (name "unconnected-(U1D-PA22{slash}ADTRG{slash}ETXER-Pad207)") (class "Default")
      (node (ref "U1") (pin "207") (pinfunction "PA22/ADTRG/ETXER_207") (pintype "bidirectional+no_connect"))
    )
    (net (code "171") (name "unconnected-(U1E-ISI_D0{slash}RK0{slash}PB20-Pad163)") (class "Default")
      (node (ref "U1") (pin "163") (pinfunction "ISI_D0/RK0/PB20_163") (pintype "bidirectional+no_connect"))
    )
    (net (code "172") (name "unconnected-(U1E-ISI_D8{slash}TXD3{slash}PB10-Pad161)") (class "Default")
      (node (ref "U1") (pin "161") (pinfunction "ISI_D8/TXD3/PB10_161") (pintype "bidirectional+no_connect"))
    )
    (net (code "173") (name "unconnected-(U1E-ISI_D9{slash}RXD3{slash}PB11-Pad162)") (class "Default")
      (node (ref "U1") (pin "162") (pinfunction "ISI_D9/RXD3/PB11_162") (pintype "bidirectional+no_connect"))
    )
    (net (code "174") (name "unconnected-(U1F-CTS3{slash}A25_CFRNW{slash}PC10-Pad58)") (class "Default")
      (node (ref "U1") (pin "58") (pinfunction "CTS3/A25_CFRNW/PC10_58") (pintype "bidirectional+no_connect"))
    )
    (net (code "175") (name "unconnected-(U1F-IRQ1{slash}NWAIT{slash}PC15-Pad127)") (class "Default")
      (node (ref "U1") (pin "127") (pinfunction "IRQ1/NWAIT/PC15_127") (pintype "bidirectional+no_connect"))
    )
    (net (code "176") (name "unconnected-(U1F-PCK0{slash}AD1{slash}PC1-Pad159)") (class "Default")
      (node (ref "U1") (pin "159") (pinfunction "PCK0/AD1/PC1_159") (pintype "bidirectional+no_connect"))
    )
    (net (code "177") (name "unconnected-(U1F-SCK3{slash}AD0{slash}PC0-Pad158)") (class "Default")
      (node (ref "U1") (pin "158") (pinfunction "SCK3/AD0/PC0_158") (pintype "bidirectional+no_connect"))
    )
  )
)
